# shield.net
KiCad netlist of a schematic drawn in EAGLE
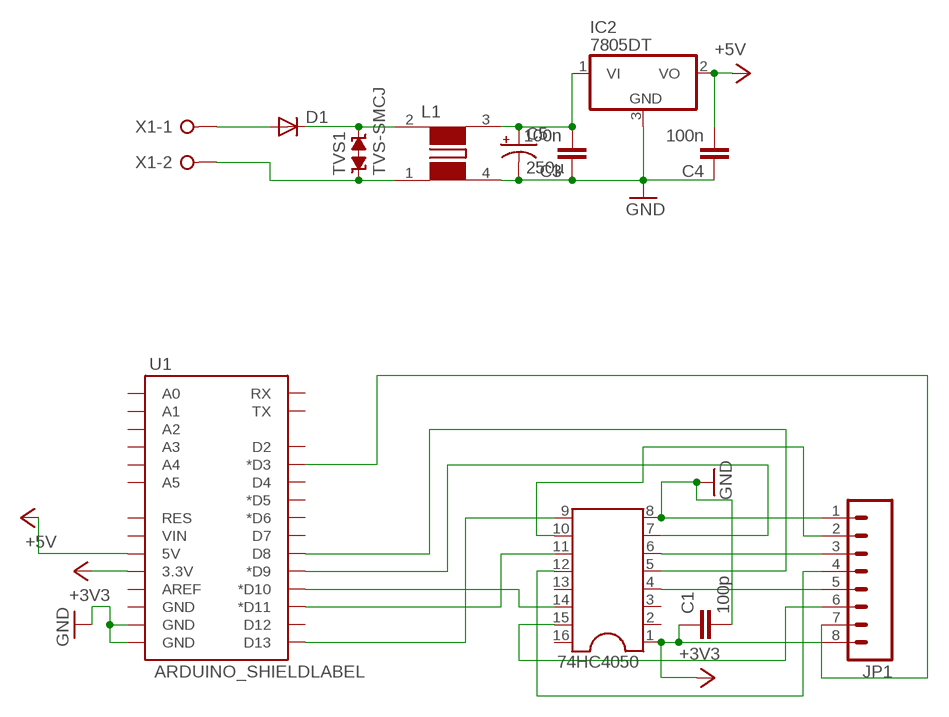
[diagram p0: schematic, sheet 1]

(export (version "E")
  (design (tool "Eeschema 10.0.6"))
  (components
    (comp (ref "74HC4050")
      (value "DIL16")
      (footprint "eagle-import:DIL16")
      (libsource (lib "eagle-import") (part "DIL16"))
    )
    (comp (ref "C1")
      (value "100p")
      (footprint "eagle-import:C0603K")
      (libsource (lib "eagle-import") (part "C-EUC0603K"))
    )
    (comp (ref "C3")
      (value "100n")
      (footprint "eagle-import:C1206K")
      (libsource (lib "eagle-import") (part "C-EUC1206K"))
    )
    (comp (ref "C4")
      (value "100n")
      (footprint "eagle-import:C1206K")
      (libsource (lib "eagle-import") (part "C-EUC1206K"))
    )
    (comp (ref "C5")
      (value "250µ")
      (footprint "eagle-import:PANASONIC_H13")
      (libsource (lib "eagle-import") (part "CAP_POLH13"))
    )
    (comp (ref "D1")
      (value "DIODE-DO-214AC")
      (footprint "eagle-import:DO-214AC")
      (libsource (lib "eagle-import") (part "DIODE-DO-214AC"))
    )
    (comp (ref "IC2")
      (value "7805DT")
      (footprint "eagle-import:TO252")
      (libsource (lib "eagle-import") (part "78DT05"))
    )
    (comp (ref "JP1")
      (value "M083.5MM-8")
      (footprint "eagle-import:SCREWTERMINAL-3.5MM-8")
      (libsource (lib "eagle-import") (part "M083.5MM-8"))
    )
    (comp (ref "L1")
      (value "WE-SL2")
      (footprint "eagle-import:WE-SL2_74422...")
      (libsource (lib "eagle-import") (part "WE-SL2"))
    )
    (comp (ref "TVS1")
      (value "TVS-SMCJ")
      (footprint "eagle-import:SMCJ")
      (libsource (lib "eagle-import") (part "TVS-SMCJ"))
    )
    (comp (ref "U1")
      (value "ARDUINO_SHIELDLABEL")
      (footprint "eagle-import:DUEMILANOVE_SHIELD")
      (libsource (lib "eagle-import") (part "ARDUINO_SHIELDLABEL"))
    )
    (comp (ref "X1")
      (value "W237-02P")
      (footprint "eagle-import:W237-132")
      (libsource (lib "eagle-import") (part "W237-02P"))
    )
  )
  (nets
    (net (code "1") (name "+3V3") (class "Default")
      (node (ref "74HC4050") (pin "1") (pinfunction "1_1") (pintype "passive"))
      (node (ref "C1") (pin "1") (pinfunction "1_1") (pintype "passive"))
      (node (ref "JP1") (pin "8") (pinfunction "8_8") (pintype "passive"))
      (node (ref "U1") (pin "3.3V") (pinfunction "3.3V_3.3V") (pintype "bidirectional"))
    )
    (net (code "2") (name "+5V") (class "Default")
      (node (ref "C4") (pin "2") (pinfunction "2_2") (pintype "passive"))
      (node (ref "IC2") (pin "2") (pinfunction "VO_2") (pintype "passive"))
      (node (ref "U1") (pin "5V") (pinfunction "5V_5V") (pintype "bidirectional"))
    )
    (net (code "3") (name "GND") (class "Default")
      (node (ref "74HC4050") (pin "8") (pinfunction "8_8") (pintype "passive"))
      (node (ref "C1") (pin "2") (pinfunction "2_2") (pintype "passive"))
      (node (ref "C3") (pin "1") (pinfunction "1_1") (pintype "passive"))
      (node (ref "C4") (pin "1") (pinfunction "1_1") (pintype "passive"))
      (node (ref "C5") (pin "-") (pinfunction "-_-") (pintype "passive"))
      (node (ref "IC2") (pin "3") (pinfunction "GND_3") (pintype "passive"))
      (node (ref "JP1") (pin "1") (pinfunction "1_1") (pintype "passive"))
      (node (ref "L1") (pin "4") (pinfunction "3_4") (pintype "passive"))
      (node (ref "U1") (pin "GND@0") (pinfunction "GND_GND@0") (pintype "bidirectional"))
      (node (ref "U1") (pin "GND@1") (pinfunction "GND_GND@1") (pintype "bidirectional"))
    )
    (net (code "4") (name "Net-(74HC4050-Pad4)") (class "Default")
      (node (ref "74HC4050") (pin "4") (pinfunction "4_4") (pintype "passive"))
      (node (ref "JP1") (pin "5") (pinfunction "5_5") (pintype "passive"))
    )
    (net (code "5") (name "Net-(74HC4050-Pad5)") (class "Default")
      (node (ref "74HC4050") (pin "5") (pinfunction "5_5") (pintype "passive"))
      (node (ref "U1") (pin "D8") (pinfunction "D8_D8") (pintype "bidirectional"))
    )
    (net (code "6") (name "Net-(74HC4050-Pad6)") (class "Default")
      (node (ref "74HC4050") (pin "6") (pinfunction "6_6") (pintype "passive"))
      (node (ref "JP1") (pin "3") (pinfunction "3_3") (pintype "passive"))
    )
    (net (code "7") (name "Net-(74HC4050-Pad9)") (class "Default")
      (node (ref "74HC4050") (pin "9") (pinfunction "9_9") (pintype "passive"))
      (node (ref "U1") (pin "D13") (pinfunction "D13_D13") (pintype "bidirectional"))
    )
    (net (code "8") (name "Net-(74HC4050-Pad10)") (class "Default")
      (node (ref "74HC4050") (pin "10") (pinfunction "10_10") (pintype "passive"))
      (node (ref "JP1") (pin "2") (pinfunction "2_2") (pintype "passive"))
    )
    (net (code "9") (name "Net-(74HC4050-Pad12)") (class "Default")
      (node (ref "74HC4050") (pin "12") (pinfunction "12_12") (pintype "passive"))
      (node (ref "JP1") (pin "4") (pinfunction "4_4") (pintype "passive"))
    )
    (net (code "10") (name "Net-(74HC4050-Pad15)") (class "Default")
      (node (ref "74HC4050") (pin "15") (pinfunction "15_15") (pintype "passive"))
      (node (ref "JP1") (pin "6") (pinfunction "6_6") (pintype "passive"))
    )
    (net (code "11") (name "Net-(IC2-VI)") (class "Default")
      (node (ref "C3") (pin "2") (pinfunction "2_2") (pintype "passive"))
      (node (ref "C5") (pin "+") (pinfunction "+_+") (pintype "passive"))
      (node (ref "IC2") (pin "1") (pinfunction "VI_1") (pintype "input"))
      (node (ref "L1") (pin "3") (pinfunction "4_3") (pintype "passive"))
    )
    (net (code "12") (name "Net-(L1-1)") (class "Default")
      (node (ref "D1") (pin "C") (pinfunction "C_C") (pintype "passive"))
      (node (ref "L1") (pin "2") (pinfunction "1_2") (pintype "passive"))
      (node (ref "TVS1") (pin "C") (pinfunction "2_C") (pintype "passive"))
    )
    (net (code "13") (name "Net-(L1-2)") (class "Default")
      (node (ref "L1") (pin "1") (pinfunction "2_1") (pintype "passive"))
      (node (ref "TVS1") (pin "A") (pinfunction "1_A") (pintype "passive"))
      (node (ref "X1") (pin "2") (pinfunction "KL_2") (pintype "passive"))
    )
    (net (code "14") (name "Net-(U1-*D3)") (class "Default")
      (node (ref "JP1") (pin "7") (pinfunction "7_7") (pintype "passive"))
      (node (ref "U1") (pin "D3") (pinfunction "*D3_D3") (pintype "bidirectional"))
    )
    (net (code "15") (name "Net-(U1-*D9)") (class "Default")
      (node (ref "74HC4050") (pin "7") (pinfunction "7_7") (pintype "passive"))
      (node (ref "U1") (pin "D9") (pinfunction "*D9_D9") (pintype "bidirectional"))
    )
    (net (code "16") (name "Net-(U1-*D10)") (class "Default")
      (node (ref "74HC4050") (pin "14") (pinfunction "14_14") (pintype "passive"))
      (node (ref "U1") (pin "D10") (pinfunction "*D10_D10") (pintype "bidirectional"))
    )
    (net (code "17") (name "Net-(U1-*D11)") (class "Default")
      (node (ref "74HC4050") (pin "11") (pinfunction "11_11") (pintype "passive"))
      (node (ref "U1") (pin "D11") (pinfunction "*D11_D11") (pintype "bidirectional"))
    )
    (net (code "18") (name "Net-(X1A-KL)") (class "Default")
      (node (ref "D1") (pin "A") (pinfunction "A_A") (pintype "passive"))
      (node (ref "X1") (pin "1") (pinfunction "KL_1") (pintype "passive"))
    )
    (net (code "19") (name "unconnected-(74HC4050-Pad2)") (class "Default")
      (node (ref "74HC4050") (pin "2") (pinfunction "2_2") (pintype "passive"))
    )
    (net (code "20") (name "unconnected-(74HC4050-Pad3)") (class "Default")
      (node (ref "74HC4050") (pin "3") (pinfunction "3_3") (pintype "passive"))
    )
    (net (code "21") (name "unconnected-(74HC4050-Pad13)") (class "Default")
      (node (ref "74HC4050") (pin "13") (pinfunction "13_13") (pintype "passive"))
    )
    (net (code "22") (name "unconnected-(74HC4050-Pad16)") (class "Default")
      (node (ref "74HC4050") (pin "16") (pinfunction "16_16") (pintype "passive"))
    )
    (net (code "23") (name "unconnected-(U1-*D5-PadD5)") (class "Default")
      (node (ref "U1") (pin "D5") (pinfunction "*D5_D5") (pintype "bidirectional"))
    )
    (net (code "24") (name "unconnected-(U1-*D6-PadD6)") (class "Default")
      (node (ref "U1") (pin "D6") (pinfunction "*D6_D6") (pintype "bidirectional"))
    )
    (net (code "25") (name "unconnected-(U1-GND-PadGND@2)") (class "Default")
      (node (ref "U1") (pin "GND@2") (pinfunction "GND_GND@2") (pintype "bidirectional"))
    )
    (net (code "26") (name "unconnected-(U1-PadA0)") (class "Default")
      (node (ref "U1") (pin "A0") (pinfunction "A0_A0") (pintype "bidirectional"))
    )
    (net (code "27") (name "unconnected-(U1-PadA1)") (class "Default")
      (node (ref "U1") (pin "A1") (pinfunction "A1_A1") (pintype "bidirectional"))
    )
    (net (code "28") (name "unconnected-(U1-PadA2)") (class "Default")
      (node (ref "U1") (pin "A2") (pinfunction "A2_A2") (pintype "bidirectional"))
    )
    (net (code "29") (name "unconnected-(U1-PadA3)") (class "Default")
      (node (ref "U1") (pin "A3") (pinfunction "A3_A3") (pintype "bidirectional"))
    )
    (net (code "30") (name "unconnected-(U1-PadA4)") (class "Default")
      (node (ref "U1") (pin "A4") (pinfunction "A4_A4") (pintype "bidirectional"))
    )
    (net (code "31") (name "unconnected-(U1-PadA5)") (class "Default")
      (node (ref "U1") (pin "A5") (pinfunction "A5_A5") (pintype "bidirectional"))
    )
    (net (code "32") (name "unconnected-(U1-PadAREF)") (class "Default")
      (node (ref "U1") (pin "AREF") (pinfunction "AREF_AREF") (pintype "bidirectional"))
    )
    (net (code "33") (name "unconnected-(U1-PadD2)") (class "Default")
      (node (ref "U1") (pin "D2") (pinfunction "D2_D2") (pintype "bidirectional"))
    )
    (net (code "34") (name "unconnected-(U1-PadD4)") (class "Default")
      (node (ref "U1") (pin "D4") (pinfunction "D4_D4") (pintype "bidirectional"))
    )
    (net (code "35") (name "unconnected-(U1-PadD7)") (class "Default")
      (node (ref "U1") (pin "D7") (pinfunction "D7_D7") (pintype "bidirectional"))
    )
    (net (code "36") (name "unconnected-(U1-PadD12)") (class "Default")
      (node (ref "U1") (pin "D12") (pinfunction "D12_D12") (pintype "bidirectional"))
    )
    (net (code "37") (name "unconnected-(U1-PadRES)") (class "Default")
      (node (ref "U1") (pin "RES") (pinfunction "RES_RES") (pintype "bidirectional"))
    )
    (net (code "38") (name "unconnected-(U1-PadRX)") (class "Default")
      (node (ref "U1") (pin "RX") (pinfunction "RX_RX") (pintype "bidirectional"))
    )
    (net (code "39") (name "unconnected-(U1-PadTX)") (class "Default")
      (node (ref "U1") (pin "TX") (pinfunction "TX_TX") (pintype "bidirectional"))
    )
    (net (code "40") (name "unconnected-(U1-PadVIN)") (class "Default")
      (node (ref "U1") (pin "VIN") (pinfunction "VIN_VIN") (pintype "bidirectional"))
    )
  )
)
